# MicroMod_Environmental.net
KiCad netlist of a schematic drawn in EAGLE
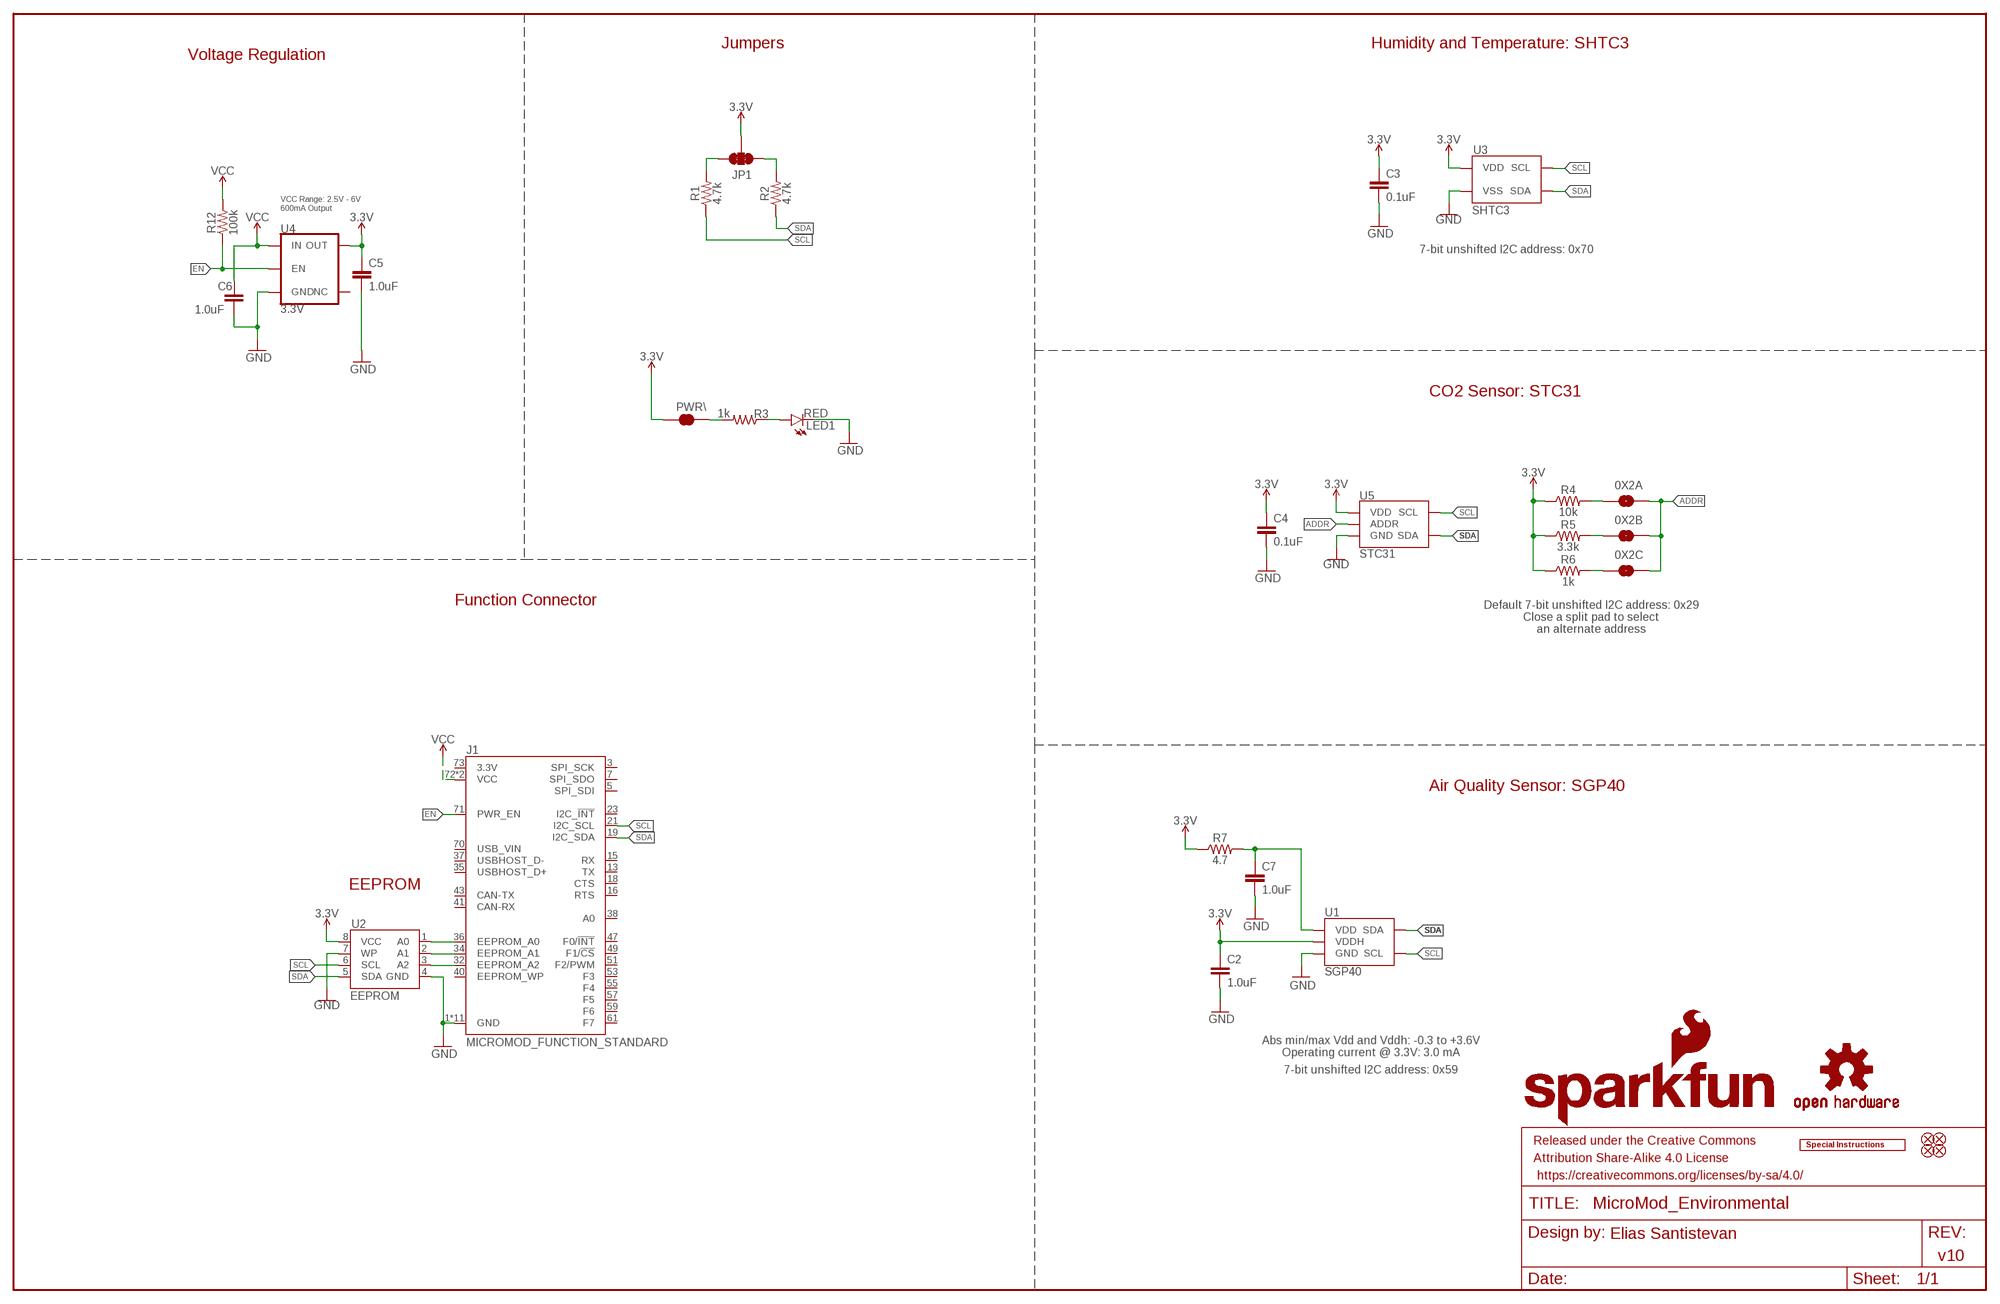
[diagram p0: schematic, sheet 1]

(export (version "E")
  (design (tool "Eeschema 10.0.6"))
  (components
    (comp (ref "0X2A")
      (value "JUMPER-SMT_2_NO_SILK")
      (footprint "eagle-import:SMT-JUMPER_2_NO_SILK")
      (libsource (lib "eagle-import") (part "JUMPER-SMT_2_NO_SILK"))
    )
    (comp (ref "0X2B")
      (value "JUMPER-SMT_2_NO_SILK")
      (footprint "eagle-import:SMT-JUMPER_2_NO_SILK")
      (libsource (lib "eagle-import") (part "JUMPER-SMT_2_NO_SILK"))
    )
    (comp (ref "0X2C")
      (value "JUMPER-SMT_2_NO_SILK")
      (footprint "eagle-import:SMT-JUMPER_2_NO_SILK")
      (libsource (lib "eagle-import") (part "JUMPER-SMT_2_NO_SILK"))
    )
    (comp (ref "C2")
      (value "1.0uF")
      (footprint "eagle-import:0603")
      (libsource (lib "eagle-import") (part "1.0UF-0603-16V-10%-X7R"))
    )
    (comp (ref "C3")
      (value "0.1uF")
      (footprint "eagle-import:0603")
      (libsource (lib "eagle-import") (part "0.1UF-0603-25V-5%"))
    )
    (comp (ref "C4")
      (value "0.1uF")
      (footprint "eagle-import:0603")
      (libsource (lib "eagle-import") (part "0.1UF-0603-25V-5%"))
    )
    (comp (ref "C5")
      (value "1.0uF")
      (footprint "eagle-import:0603")
      (libsource (lib "eagle-import") (part "1.0UF-0603-16V-10%"))
    )
    (comp (ref "C6")
      (value "1.0uF")
      (footprint "eagle-import:0603")
      (libsource (lib "eagle-import") (part "1.0UF-0603-16V-10%"))
    )
    (comp (ref "C7")
      (value "1.0uF")
      (footprint "eagle-import:0603")
      (libsource (lib "eagle-import") (part "1.0UF-0603-16V-10%-X7R"))
    )
    (comp (ref "FD1")
      (value "FIDUCIAL1X2")
      (footprint "eagle-import:FIDUCIAL-1X2")
      (libsource (lib "eagle-import") (part "FIDUCIAL1X2"))
    )
    (comp (ref "FD2")
      (value "FIDUCIAL1X2")
      (footprint "eagle-import:FIDUCIAL-1X2")
      (libsource (lib "eagle-import") (part "FIDUCIAL1X2"))
    )
    (comp (ref "FD3")
      (value "FIDUCIAL1X2")
      (footprint "eagle-import:FIDUCIAL-1X2")
      (libsource (lib "eagle-import") (part "FIDUCIAL1X2"))
    )
    (comp (ref "FD4")
      (value "FIDUCIAL1X2")
      (footprint "eagle-import:FIDUCIAL-1X2")
      (libsource (lib "eagle-import") (part "FIDUCIAL1X2"))
    )
    (comp (ref "FRAME1")
      (value "FRAME-LEDGER")
      (footprint "eagle-import:CREATIVE_COMMONS")
      (libsource (lib "eagle-import") (part "FRAME-LEDGER"))
    )
    (comp (ref "J1")
      (value "MICROMOD_FUNCTION_STANDARD")
      (footprint "eagle-import:M.2-CARD-E-22_FUNCTION_STANDARD")
      (libsource (lib "eagle-import") (part "MICROMOD_FUNCTION_STANDARD"))
    )
    (comp (ref "JP1")
      (value "JUMPER-SMT_3_2-NC_TRACE_SILK")
      (footprint "eagle-import:SMT-JUMPER_3_2-NC_TRACE_SILK")
      (libsource (lib "eagle-import") (part "JUMPER-SMT_3_2-NC_TRACE_SILK"))
    )
    (comp (ref "LED1")
      (value "RED")
      (footprint "eagle-import:LED-0603")
      (libsource (lib "eagle-import") (part "LED-RED0603"))
    )
    (comp (ref "LOGO1")
      (value "SFE_LOGO_NAME_FLAME.2_INCH")
      (footprint "eagle-import:SFE_LOGO_NAME_FLAME_.2")
      (libsource (lib "eagle-import") (part "SFE_LOGO_NAME_FLAME.2_INCH"))
    )
    (comp (ref "LOGO2")
      (value "OSHW-LOGOS")
      (footprint "eagle-import:OSHW-LOGO-S")
      (libsource (lib "eagle-import") (part "OSHW-LOGOS"))
    )
    (comp (ref "LOGO3")
      (value "SPECIAL_INSTRUCTIONS-ORDERING")
      (footprint "eagle-import:ORDERING_INSTRUCTIONS")
      (libsource (lib "eagle-import") (part "SPECIAL_INSTRUCTIONS-ORDERING"))
    )
    (comp (ref "PWR\\")
      (value "JUMPER-SMT_2_NC_TRACE_SILK")
      (footprint "eagle-import:SMT-JUMPER_2_NC_TRACE_SILK")
      (libsource (lib "eagle-import") (part "JUMPER-SMT_2_NC_TRACE_SILK"))
    )
    (comp (ref "R1")
      (value "4.7k")
      (footprint "eagle-import:0603")
      (libsource (lib "eagle-import") (part "4.7KOHM-0603-1/10W-1%"))
    )
    (comp (ref "R2")
      (value "4.7k")
      (footprint "eagle-import:0603")
      (libsource (lib "eagle-import") (part "4.7KOHM-0603-1/10W-1%"))
    )
    (comp (ref "R3")
      (value "1k")
      (footprint "eagle-import:0603")
      (libsource (lib "eagle-import") (part "1KOHM-0603-1/10W-1%"))
    )
    (comp (ref "R4")
      (value "10k")
      (footprint "eagle-import:0603")
      (libsource (lib "eagle-import") (part "10KOHM-0603-1/10W-1%"))
    )
    (comp (ref "R5")
      (value "3.3k")
      (footprint "eagle-import:0603")
      (libsource (lib "eagle-import") (part "3.3KOHM-0603-1/10W-1%"))
    )
    (comp (ref "R6")
      (value "1k")
      (footprint "eagle-import:0603")
      (libsource (lib "eagle-import") (part "1KOHM-0603-1/10W-1%"))
    )
    (comp (ref "R7")
      (value "4.7")
      (footprint "eagle-import:0603")
      (libsource (lib "eagle-import") (part "4.7OHM-0603-1/10W-1%"))
    )
    (comp (ref "R12")
      (value "100k")
      (footprint "eagle-import:0603")
      (libsource (lib "eagle-import") (part "100KOHM-0603-1/10W-1%"))
    )
    (comp (ref "U1")
      (value "SGP40")
      (footprint "eagle-import:SGP40")
      (fields (field (name "DIGIKEY_PART") "1649-SGP40-D-R4CT-ND"))
      (libsource (lib "eagle-import") (part "SGP40"))
    )
    (comp (ref "U2")
      (value "EEPROM")
      (footprint "eagle-import:SO08")
      (libsource (lib "eagle-import") (part "EEPROM-I2C512K"))
    )
    (comp (ref "U3")
      (value "SHTC3")
      (footprint "eagle-import:SHTC3")
      (libsource (lib "eagle-import") (part "SHTC3"))
    )
    (comp (ref "U4")
      (value "3.3V")
      (footprint "eagle-import:SOT23-5")
      (libsource (lib "eagle-import") (part "V_REG_AP2112K-3.3V"))
    )
    (comp (ref "U5")
      (value "STC31")
      (footprint "eagle-import:STC31")
      (fields (field (name "MANU_PART") "STC31-R3"))
      (libsource (lib "eagle-import") (part "STC31"))
    )
  )
  (nets
    (net (code "1") (name "3.3V") (class "Default")
      (node (ref "C2") (pin "1") (pinfunction "1_1") (pintype "passive"))
      (node (ref "C3") (pin "1") (pinfunction "1_1") (pintype "passive"))
      (node (ref "C4") (pin "1") (pinfunction "1_1") (pintype "passive"))
      (node (ref "C5") (pin "1") (pinfunction "1_1") (pintype "passive"))
      (node (ref "JP1") (pin "2") (pinfunction "2_2") (pintype "passive"))
      (node (ref "PWR\\") (pin "2") (pinfunction "2_2") (pintype "passive"))
      (node (ref "R4") (pin "1") (pinfunction "1_1") (pintype "passive"))
      (node (ref "R5") (pin "1") (pinfunction "1_1") (pintype "passive"))
      (node (ref "R6") (pin "1") (pinfunction "1_1") (pintype "passive"))
      (node (ref "R7") (pin "1") (pinfunction "1_1") (pintype "passive"))
      (node (ref "U1") (pin "5") (pinfunction "VDDH_5") (pintype "power_in"))
      (node (ref "U2") (pin "8") (pinfunction "VCC_8") (pintype "power_in"))
      (node (ref "U3") (pin "1") (pinfunction "VDD_1") (pintype "bidirectional"))
      (node (ref "U4") (pin "5") (pinfunction "OUT_5") (pintype "passive"))
      (node (ref "U5") (pin "6") (pinfunction "VDD_6") (pintype "power_in"))
    )
    (net (code "2") (name "ADDR") (class "Default")
      (node (ref "0X2A") (pin "2") (pinfunction "2_2") (pintype "passive"))
      (node (ref "0X2B") (pin "2") (pinfunction "2_2") (pintype "passive"))
      (node (ref "0X2C") (pin "2") (pinfunction "2_2") (pintype "passive"))
      (node (ref "U5") (pin "3") (pinfunction "ADDR_3") (pintype "bidirectional"))
    )
    (net (code "3") (name "EN") (class "Default")
      (node (ref "J1") (pin "71") (pinfunction "PWR_EN_71") (pintype "bidirectional"))
      (node (ref "R12") (pin "1") (pinfunction "1_1") (pintype "passive"))
      (node (ref "U4") (pin "3") (pinfunction "EN_3") (pintype "input"))
    )
    (net (code "4") (name "GND") (class "Default")
      (node (ref "C2") (pin "2") (pinfunction "2_2") (pintype "passive"))
      (node (ref "C3") (pin "2") (pinfunction "2_2") (pintype "passive"))
      (node (ref "C4") (pin "2") (pinfunction "2_2") (pintype "passive"))
      (node (ref "C5") (pin "2") (pinfunction "2_2") (pintype "passive"))
      (node (ref "C6") (pin "2") (pinfunction "2_2") (pintype "passive"))
      (node (ref "C7") (pin "2") (pinfunction "2_2") (pintype "passive"))
      (node (ref "J1") (pin "1") (pinfunction "GND_1") (pintype "bidirectional"))
      (node (ref "J1") (pin "33") (pinfunction "GND_33") (pintype "bidirectional"))
      (node (ref "J1") (pin "39") (pinfunction "GND_39") (pintype "bidirectional"))
      (node (ref "J1") (pin "45") (pinfunction "GND_45") (pintype "bidirectional"))
      (node (ref "J1") (pin "75") (pinfunction "GND_75") (pintype "bidirectional"))
      (node (ref "J1") (pin "GND1") (pinfunction "GND_GND1") (pintype "bidirectional"))
      (node (ref "J1") (pin "GND2") (pinfunction "GND_GND2") (pintype "bidirectional"))
      (node (ref "J1") (pin "GND3") (pinfunction "GND_GND3") (pintype "bidirectional"))
      (node (ref "J1") (pin "GND4") (pinfunction "GND_GND4") (pintype "bidirectional"))
      (node (ref "J1") (pin "GND5") (pinfunction "GND_GND5") (pintype "bidirectional"))
      (node (ref "J1") (pin "GND6") (pinfunction "GND_GND6") (pintype "bidirectional"))
      (node (ref "LED1") (pin "C") (pinfunction "C_C") (pintype "passive"))
      (node (ref "U1") (pin "2") (pinfunction "GND_2") (pintype "power_in"))
      (node (ref "U1") (pin "4") (pinfunction "GND_4") (pintype "power_in"))
      (node (ref "U1") (pin "DIEPAD") (pinfunction "GND_DIEPAD") (pintype "power_in"))
      (node (ref "U2") (pin "4") (pinfunction "GND_4") (pintype "power_in"))
      (node (ref "U2") (pin "7") (pinfunction "WP_7") (pintype "bidirectional"))
      (node (ref "U3") (pin "4") (pinfunction "VSS_4") (pintype "bidirectional"))
      (node (ref "U3") (pin "5") (pinfunction "VSS_5") (pintype "bidirectional"))
      (node (ref "U4") (pin "2") (pinfunction "GND_2") (pintype "input"))
      (node (ref "U5") (pin "1") (pinfunction "GND_1") (pintype "power_in"))
      (node (ref "U5") (pin "11") (pinfunction "GND_11") (pintype "power_in"))
      (node (ref "U5") (pin "5") (pinfunction "GND_5") (pintype "power_in"))
      (node (ref "U5") (pin "9") (pinfunction "GND_9") (pintype "power_in"))
      (node (ref "U5") (pin "DIEPAD") (pinfunction "GND_DIEPAD") (pintype "power_in"))
    )
    (net (code "5") (name "Net-(0X2A-Pad1)") (class "Default")
      (node (ref "0X2A") (pin "1") (pinfunction "1_1") (pintype "passive"))
      (node (ref "R4") (pin "2") (pinfunction "2_2") (pintype "passive"))
    )
    (net (code "6") (name "Net-(0X2B-Pad1)") (class "Default")
      (node (ref "0X2B") (pin "1") (pinfunction "1_1") (pintype "passive"))
      (node (ref "R5") (pin "2") (pinfunction "2_2") (pintype "passive"))
    )
    (net (code "7") (name "Net-(0X2C-Pad1)") (class "Default")
      (node (ref "0X2C") (pin "1") (pinfunction "1_1") (pintype "passive"))
      (node (ref "R6") (pin "2") (pinfunction "2_2") (pintype "passive"))
    )
    (net (code "8") (name "Net-(J1-EEPROM_A0)") (class "Default")
      (node (ref "J1") (pin "36") (pinfunction "EEPROM_A0_36") (pintype "bidirectional"))
      (node (ref "U2") (pin "1") (pinfunction "A0_1") (pintype "bidirectional"))
    )
    (net (code "9") (name "Net-(J1-EEPROM_A1)") (class "Default")
      (node (ref "J1") (pin "34") (pinfunction "EEPROM_A1_34") (pintype "bidirectional"))
      (node (ref "U2") (pin "2") (pinfunction "A1_2") (pintype "bidirectional"))
    )
    (net (code "10") (name "Net-(J1-EEPROM_A2)") (class "Default")
      (node (ref "J1") (pin "32") (pinfunction "EEPROM_A2_32") (pintype "bidirectional"))
      (node (ref "U2") (pin "3") (pinfunction "A2_3") (pintype "bidirectional"))
    )
    (net (code "11") (name "Net-(JP1-Pad1)") (class "Default")
      (node (ref "JP1") (pin "1") (pinfunction "1_1") (pintype "passive"))
      (node (ref "R2") (pin "2") (pinfunction "2_2") (pintype "passive"))
    )
    (net (code "12") (name "Net-(JP1-Pad3)") (class "Default")
      (node (ref "JP1") (pin "3") (pinfunction "3_3") (pintype "passive"))
      (node (ref "R1") (pin "2") (pinfunction "2_2") (pintype "passive"))
    )
    (net (code "13") (name "Net-(LED1-PadA)") (class "Default")
      (node (ref "LED1") (pin "A") (pinfunction "A_A") (pintype "passive"))
      (node (ref "R3") (pin "1") (pinfunction "1_1") (pintype "passive"))
    )
    (net (code "14") (name "Net-(PWR\\-Pad1)") (class "Default")
      (node (ref "PWR\\") (pin "1") (pinfunction "1_1") (pintype "passive"))
      (node (ref "R3") (pin "2") (pinfunction "2_2") (pintype "passive"))
    )
    (net (code "15") (name "Net-(U1-VDD)") (class "Default")
      (node (ref "C7") (pin "1") (pinfunction "1_1") (pintype "passive"))
      (node (ref "R7") (pin "2") (pinfunction "2_2") (pintype "passive"))
      (node (ref "U1") (pin "1") (pinfunction "VDD_1") (pintype "power_in"))
    )
    (net (code "16") (name "SCL") (class "Default")
      (node (ref "J1") (pin "21") (pinfunction "I2C_SCL_21") (pintype "bidirectional"))
      (node (ref "R1") (pin "1") (pinfunction "1_1") (pintype "passive"))
      (node (ref "U1") (pin "6") (pinfunction "SCL_6") (pintype "bidirectional"))
      (node (ref "U2") (pin "6") (pinfunction "SCL_6") (pintype "bidirectional"))
      (node (ref "U3") (pin "2") (pinfunction "SCL_2") (pintype "bidirectional"))
      (node (ref "U5") (pin "4") (pinfunction "SCL_4") (pintype "bidirectional"))
    )
    (net (code "17") (name "SDA") (class "Default")
      (node (ref "J1") (pin "19") (pinfunction "I2C_SDA_19") (pintype "bidirectional"))
      (node (ref "R2") (pin "1") (pinfunction "1_1") (pintype "passive"))
      (node (ref "U1") (pin "3") (pinfunction "SDA_3") (pintype "bidirectional"))
      (node (ref "U2") (pin "5") (pinfunction "SDA_5") (pintype "bidirectional"))
      (node (ref "U3") (pin "3") (pinfunction "SDA_3") (pintype "bidirectional"))
      (node (ref "U5") (pin "7") (pinfunction "SDA_7") (pintype "bidirectional"))
    )
    (net (code "18") (name "VCC") (class "Default")
      (node (ref "C6") (pin "1") (pinfunction "1_1") (pintype "passive"))
      (node (ref "J1") (pin "72") (pinfunction "VCC_72") (pintype "bidirectional"))
      (node (ref "J1") (pin "74") (pinfunction "VCC_74") (pintype "bidirectional"))
      (node (ref "R12") (pin "2") (pinfunction "2_2") (pintype "passive"))
      (node (ref "U4") (pin "1") (pinfunction "IN_1") (pintype "input"))
    )
    (net (code "19") (name "unconnected-(J1-3.3V-Pad73)") (class "Default")
      (node (ref "J1") (pin "73") (pinfunction "3.3V_73") (pintype "bidirectional"))
    )
    (net (code "20") (name "unconnected-(J1-A0-Pad38)") (class "Default")
      (node (ref "J1") (pin "38") (pinfunction "A0_38") (pintype "bidirectional"))
    )
    (net (code "21") (name "unconnected-(J1-CAN-RX-Pad41)") (class "Default")
      (node (ref "J1") (pin "41") (pinfunction "CAN-RX_41") (pintype "bidirectional"))
    )
    (net (code "22") (name "unconnected-(J1-CAN-TX-Pad43)") (class "Default")
      (node (ref "J1") (pin "43") (pinfunction "CAN-TX_43") (pintype "bidirectional"))
    )
    (net (code "23") (name "unconnected-(J1-CTS-Pad18)") (class "Default")
      (node (ref "J1") (pin "18") (pinfunction "CTS_18") (pintype "bidirectional"))
    )
    (net (code "24") (name "unconnected-(J1-EEPROM_WP-Pad40)") (class "Default")
      (node (ref "J1") (pin "40") (pinfunction "EEPROM_WP_40") (pintype "bidirectional"))
    )
    (net (code "25") (name "unconnected-(J1-F0{slash}~{INT}-Pad47)") (class "Default")
      (node (ref "J1") (pin "47") (pinfunction "F0/~{INT}_47") (pintype "bidirectional"))
    )
    (net (code "26") (name "unconnected-(J1-F1{slash}~{CS}-Pad49)") (class "Default")
      (node (ref "J1") (pin "49") (pinfunction "F1/~{CS}_49") (pintype "bidirectional"))
    )
    (net (code "27") (name "unconnected-(J1-F2{slash}PWM-Pad51)") (class "Default")
      (node (ref "J1") (pin "51") (pinfunction "F2/PWM_51") (pintype "bidirectional"))
    )
    (net (code "28") (name "unconnected-(J1-F3-Pad53)") (class "Default")
      (node (ref "J1") (pin "53") (pinfunction "F3_53") (pintype "bidirectional"))
    )
    (net (code "29") (name "unconnected-(J1-F4-Pad55)") (class "Default")
      (node (ref "J1") (pin "55") (pinfunction "F4_55") (pintype "bidirectional"))
    )
    (net (code "30") (name "unconnected-(J1-F5-Pad57)") (class "Default")
      (node (ref "J1") (pin "57") (pinfunction "F5_57") (pintype "bidirectional"))
    )
    (net (code "31") (name "unconnected-(J1-F6-Pad59)") (class "Default")
      (node (ref "J1") (pin "59") (pinfunction "F6_59") (pintype "bidirectional"))
    )
    (net (code "32") (name "unconnected-(J1-F7-Pad61)") (class "Default")
      (node (ref "J1") (pin "61") (pinfunction "F7_61") (pintype "bidirectional"))
    )
    (net (code "33") (name "unconnected-(J1-I2C_~{INT}-Pad23)") (class "Default")
      (node (ref "J1") (pin "23") (pinfunction "I2C_~{INT}_23") (pintype "bidirectional"))
    )
    (net (code "34") (name "unconnected-(J1-RTS-Pad16)") (class "Default")
      (node (ref "J1") (pin "16") (pinfunction "RTS_16") (pintype "bidirectional"))
    )
    (net (code "35") (name "unconnected-(J1-RX-Pad15)") (class "Default")
      (node (ref "J1") (pin "15") (pinfunction "RX_15") (pintype "bidirectional"))
    )
    (net (code "36") (name "unconnected-(J1-SPI_SCK-Pad3)") (class "Default")
      (node (ref "J1") (pin "3") (pinfunction "SPI_SCK_3") (pintype "bidirectional"))
    )
    (net (code "37") (name "unconnected-(J1-SPI_SDI-Pad5)") (class "Default")
      (node (ref "J1") (pin "5") (pinfunction "SPI_SDI_5") (pintype "bidirectional"))
    )
    (net (code "38") (name "unconnected-(J1-SPI_SDO-Pad7)") (class "Default")
      (node (ref "J1") (pin "7") (pinfunction "SPI_SDO_7") (pintype "bidirectional"))
    )
    (net (code "39") (name "unconnected-(J1-TX-Pad13)") (class "Default")
      (node (ref "J1") (pin "13") (pinfunction "TX_13") (pintype "bidirectional"))
    )
    (net (code "40") (name "unconnected-(J1-USBHOST_D+-Pad35)") (class "Default")
      (node (ref "J1") (pin "35") (pinfunction "USBHOST_D+_35") (pintype "bidirectional"))
    )
    (net (code "41") (name "unconnected-(J1-USBHOST_D--Pad37)") (class "Default")
      (node (ref "J1") (pin "37") (pinfunction "USBHOST_D-_37") (pintype "bidirectional"))
    )
    (net (code "42") (name "unconnected-(J1-USB_VIN-Pad70)") (class "Default")
      (node (ref "J1") (pin "70") (pinfunction "USB_VIN_70") (pintype "bidirectional"))
    )
    (net (code "43") (name "unconnected-(U4-NC-Pad4)") (class "Default")
      (node (ref "U4") (pin "4") (pinfunction "NC_4") (pintype "no_connect"))
    )
  )
)
